# JCarlos_e_Renato.net
KiCad netlist of a schematic drawn in EAGLE
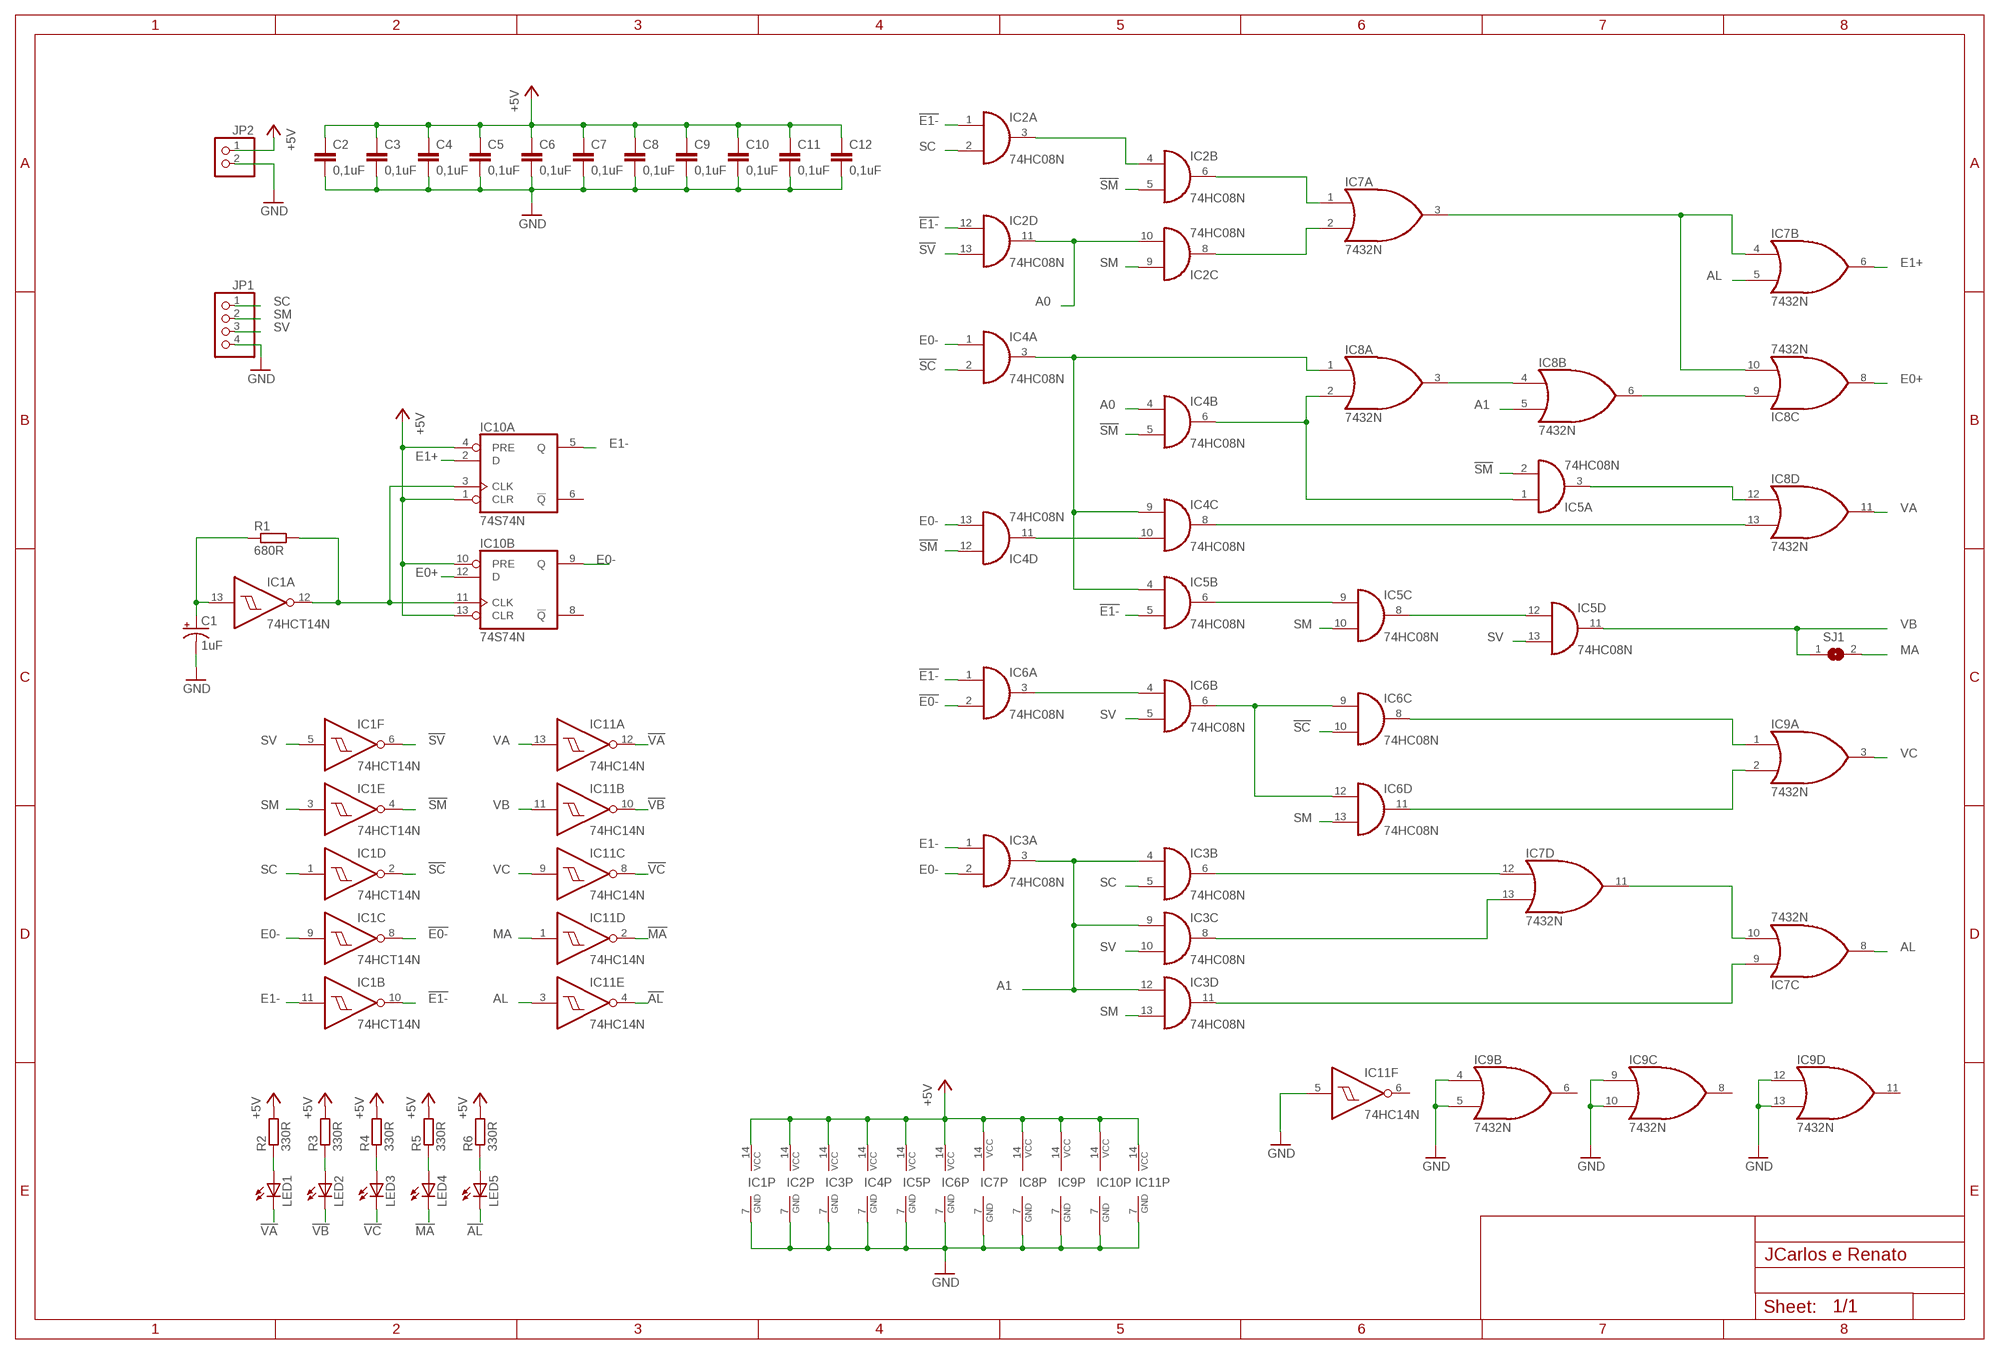
[diagram p0: schematic, sheet 1]

(export (version "E")
  (design (tool "Eeschema 10.0.6"))
  (components
    (comp (ref "C1")
      (value "1uF")
      (footprint "eagle-import:E5-6")
      (libsource (lib "eagle-import") (part "CPOL-USE5-6"))
    )
    (comp (ref "C2")
      (value "0,1uF")
      (footprint "eagle-import:C050-025X075")
      (libsource (lib "eagle-import") (part "C-EU050-025X075"))
    )
    (comp (ref "C3")
      (value "0,1uF")
      (footprint "eagle-import:C050-025X075")
      (libsource (lib "eagle-import") (part "C-EU050-025X075"))
    )
    (comp (ref "C4")
      (value "0,1uF")
      (footprint "eagle-import:C050-025X075")
      (libsource (lib "eagle-import") (part "C-EU050-025X075"))
    )
    (comp (ref "C5")
      (value "0,1uF")
      (footprint "eagle-import:C050-025X075")
      (libsource (lib "eagle-import") (part "C-EU050-025X075"))
    )
    (comp (ref "C6")
      (value "0,1uF")
      (footprint "eagle-import:C050-025X075")
      (libsource (lib "eagle-import") (part "C-EU050-025X075"))
    )
    (comp (ref "C7")
      (value "0,1uF")
      (footprint "eagle-import:C050-025X075")
      (libsource (lib "eagle-import") (part "C-EU050-025X075"))
    )
    (comp (ref "C8")
      (value "0,1uF")
      (footprint "eagle-import:C050-025X075")
      (libsource (lib "eagle-import") (part "C-EU050-025X075"))
    )
    (comp (ref "C9")
      (value "0,1uF")
      (footprint "eagle-import:C050-025X075")
      (libsource (lib "eagle-import") (part "C-EU050-025X075"))
    )
    (comp (ref "C10")
      (value "0,1uF")
      (footprint "eagle-import:C050-025X075")
      (libsource (lib "eagle-import") (part "C-EU050-025X075"))
    )
    (comp (ref "C11")
      (value "0,1uF")
      (footprint "eagle-import:C050-025X075")
      (libsource (lib "eagle-import") (part "C-EU050-025X075"))
    )
    (comp (ref "C12")
      (value "0,1uF")
      (footprint "eagle-import:C050-025X075")
      (libsource (lib "eagle-import") (part "C-EU050-025X075"))
    )
    (comp (ref "IC1")
      (value "74HCT14N")
      (footprint "eagle-import:DIL14")
      (libsource (lib "eagle-import") (part "7414NHCT"))
    )
    (comp (ref "IC2")
      (value "74HC08N")
      (footprint "eagle-import:DIL14")
      (libsource (lib "eagle-import") (part "7408NHC"))
    )
    (comp (ref "IC3")
      (value "74HC08N")
      (footprint "eagle-import:DIL14")
      (libsource (lib "eagle-import") (part "7408NHC"))
    )
    (comp (ref "IC4")
      (value "74HC08N")
      (footprint "eagle-import:DIL14")
      (libsource (lib "eagle-import") (part "7408NHC"))
    )
    (comp (ref "IC5")
      (value "74HC08N")
      (footprint "eagle-import:DIL14")
      (libsource (lib "eagle-import") (part "7408NHC"))
    )
    (comp (ref "IC6")
      (value "74HC08N")
      (footprint "eagle-import:DIL14")
      (libsource (lib "eagle-import") (part "7408NHC"))
    )
    (comp (ref "IC7")
      (value "7432N")
      (footprint "eagle-import:DIL14")
      (libsource (lib "eagle-import") (part "7432N"))
    )
    (comp (ref "IC8")
      (value "7432N")
      (footprint "eagle-import:DIL14")
      (libsource (lib "eagle-import") (part "7432N"))
    )
    (comp (ref "IC9")
      (value "7432N")
      (footprint "eagle-import:DIL14")
      (libsource (lib "eagle-import") (part "7432N"))
    )
    (comp (ref "IC10")
      (value "74S74N")
      (footprint "eagle-import:DIL14")
      (libsource (lib "eagle-import") (part "7474NS"))
    )
    (comp (ref "IC11")
      (value "74HC14N")
      (footprint "eagle-import:DIL14")
      (libsource (lib "eagle-import") (part "7414NHC"))
    )
    (comp (ref "JP1")
      (value "PINHD-1X4")
      (footprint "eagle-import:1X04")
      (libsource (lib "eagle-import") (part "PINHD-1X4"))
    )
    (comp (ref "JP2")
      (value "PINHD-1X2")
      (footprint "eagle-import:1X02")
      (libsource (lib "eagle-import") (part "PINHD-1X2"))
    )
    (comp (ref "LED1")
      (value "LED5MM")
      (footprint "eagle-import:LED5MM")
      (libsource (lib "eagle-import") (part "LED5MM"))
    )
    (comp (ref "LED2")
      (value "LED5MM")
      (footprint "eagle-import:LED5MM")
      (libsource (lib "eagle-import") (part "LED5MM"))
    )
    (comp (ref "LED3")
      (value "LED5MM")
      (footprint "eagle-import:LED5MM")
      (libsource (lib "eagle-import") (part "LED5MM"))
    )
    (comp (ref "LED4")
      (value "LED5MM")
      (footprint "eagle-import:LED5MM")
      (libsource (lib "eagle-import") (part "LED5MM"))
    )
    (comp (ref "LED5")
      (value "LED5MM")
      (footprint "eagle-import:LED5MM")
      (libsource (lib "eagle-import") (part "LED5MM"))
    )
    (comp (ref "R1")
      (value "680R")
      (footprint "eagle-import:0204_5")
      (libsource (lib "eagle-import") (part "R-EU_0204/5"))
    )
    (comp (ref "R2")
      (value "330R")
      (footprint "eagle-import:0207_10")
      (libsource (lib "eagle-import") (part "R-EU_0207/10"))
    )
    (comp (ref "R3")
      (value "330R")
      (footprint "eagle-import:0207_10")
      (libsource (lib "eagle-import") (part "R-EU_0207/10"))
    )
    (comp (ref "R4")
      (value "330R")
      (footprint "eagle-import:0207_10")
      (libsource (lib "eagle-import") (part "R-EU_0207/10"))
    )
    (comp (ref "R5")
      (value "330R")
      (footprint "eagle-import:0207_10")
      (libsource (lib "eagle-import") (part "R-EU_0207/10"))
    )
    (comp (ref "R6")
      (value "330R")
      (footprint "eagle-import:0207_10")
      (libsource (lib "eagle-import") (part "R-EU_0207/10"))
    )
    (comp (ref "SJ1") (value "SJ") (footprint "eagle-import:SJ") (libsource (lib "eagle-import") (part "SJ")))
  )
  (nets
    (net (code "1") (name "+5V") (class "Default")
      (node (ref "C10") (pin "1") (pinfunction "1_1") (pintype "passive"))
      (node (ref "C11") (pin "1") (pinfunction "1_1") (pintype "passive"))
      (node (ref "C12") (pin "1") (pinfunction "1_1") (pintype "passive"))
      (node (ref "C2") (pin "1") (pinfunction "1_1") (pintype "passive"))
      (node (ref "C3") (pin "1") (pinfunction "1_1") (pintype "passive"))
      (node (ref "C4") (pin "1") (pinfunction "1_1") (pintype "passive"))
      (node (ref "C5") (pin "1") (pinfunction "1_1") (pintype "passive"))
      (node (ref "C6") (pin "1") (pinfunction "1_1") (pintype "passive"))
      (node (ref "C7") (pin "1") (pinfunction "1_1") (pintype "passive"))
      (node (ref "C8") (pin "1") (pinfunction "1_1") (pintype "passive"))
      (node (ref "C9") (pin "1") (pinfunction "1_1") (pintype "passive"))
      (node (ref "IC1") (pin "14") (pinfunction "VCC_14") (pintype "power_in"))
      (node (ref "IC10") (pin "1") (pinfunction "CLR_1") (pintype "input"))
      (node (ref "IC10") (pin "10") (pinfunction "PRE_10") (pintype "input"))
      (node (ref "IC10") (pin "13") (pinfunction "CLR_13") (pintype "input"))
      (node (ref "IC10") (pin "14") (pinfunction "VCC_14") (pintype "power_in"))
      (node (ref "IC10") (pin "4") (pinfunction "PRE_4") (pintype "input"))
      (node (ref "IC11") (pin "14") (pinfunction "VCC_14") (pintype "power_in"))
      (node (ref "IC2") (pin "14") (pinfunction "VCC_14") (pintype "power_in"))
      (node (ref "IC3") (pin "14") (pinfunction "VCC_14") (pintype "power_in"))
      (node (ref "IC4") (pin "14") (pinfunction "VCC_14") (pintype "power_in"))
      (node (ref "IC5") (pin "14") (pinfunction "VCC_14") (pintype "power_in"))
      (node (ref "IC6") (pin "14") (pinfunction "VCC_14") (pintype "power_in"))
      (node (ref "IC7") (pin "14") (pinfunction "VCC_14") (pintype "power_in"))
      (node (ref "IC8") (pin "14") (pinfunction "VCC_14") (pintype "power_in"))
      (node (ref "IC9") (pin "14") (pinfunction "VCC_14") (pintype "power_in"))
      (node (ref "JP2") (pin "1") (pinfunction "1_1") (pintype "passive"))
      (node (ref "R2") (pin "2") (pinfunction "2_2") (pintype "passive"))
      (node (ref "R3") (pin "2") (pinfunction "2_2") (pintype "passive"))
      (node (ref "R4") (pin "2") (pinfunction "2_2") (pintype "passive"))
      (node (ref "R5") (pin "2") (pinfunction "2_2") (pintype "passive"))
      (node (ref "R6") (pin "2") (pinfunction "2_2") (pintype "passive"))
    )
    (net (code "2") (name "/A0") (class "Default")
      (node (ref "IC2") (pin "10") (pinfunction "I1_10") (pintype "input"))
      (node (ref "IC2") (pin "11") (pinfunction "O_11") (pintype "output"))
      (node (ref "IC4") (pin "4") (pinfunction "I0_4") (pintype "input"))
    )
    (net (code "3") (name "/A1") (class "Default")
      (node (ref "IC3") (pin "12") (pinfunction "I0_12") (pintype "input"))
      (node (ref "IC3") (pin "3") (pinfunction "O_3") (pintype "output"))
      (node (ref "IC3") (pin "4") (pinfunction "I0_4") (pintype "input"))
      (node (ref "IC3") (pin "9") (pinfunction "I0_9") (pintype "input"))
      (node (ref "IC8") (pin "5") (pinfunction "I1_5") (pintype "input"))
    )
    (net (code "4") (name "/AL") (class "Default")
      (node (ref "IC11") (pin "3") (pinfunction "I_3") (pintype "input"))
      (node (ref "IC7") (pin "5") (pinfunction "I1_5") (pintype "input"))
      (node (ref "IC7") (pin "8") (pinfunction "O_8") (pintype "output"))
    )
    (net (code "5") (name "/E0+") (class "Default")
      (node (ref "IC10") (pin "12") (pinfunction "D_12") (pintype "input"))
      (node (ref "IC8") (pin "8") (pinfunction "O_8") (pintype "output"))
    )
    (net (code "6") (name "/E0-") (class "Default")
      (node (ref "IC1") (pin "9") (pinfunction "I_9") (pintype "input"))
      (node (ref "IC10") (pin "9") (pinfunction "Q_9") (pintype "output"))
      (node (ref "IC3") (pin "2") (pinfunction "I1_2") (pintype "input"))
      (node (ref "IC4") (pin "1") (pinfunction "I0_1") (pintype "input"))
      (node (ref "IC4") (pin "13") (pinfunction "I1_13") (pintype "input"))
    )
    (net (code "7") (name "/E1+") (class "Default")
      (node (ref "IC10") (pin "2") (pinfunction "D_2") (pintype "input"))
      (node (ref "IC7") (pin "6") (pinfunction "O_6") (pintype "output"))
    )
    (net (code "8") (name "/E1-") (class "Default")
      (node (ref "IC1") (pin "11") (pinfunction "I_11") (pintype "input"))
      (node (ref "IC10") (pin "5") (pinfunction "Q_5") (pintype "output"))
      (node (ref "IC3") (pin "1") (pinfunction "I0_1") (pintype "input"))
    )
    (net (code "9") (name "/MA") (class "Default")
      (node (ref "IC11") (pin "1") (pinfunction "I_1") (pintype "input"))
      (node (ref "SJ1") (pin "2") (pinfunction "2_2") (pintype "passive"))
    )
    (net (code "10") (name "/SC") (class "Default")
      (node (ref "IC1") (pin "1") (pinfunction "I_1") (pintype "input"))
      (node (ref "IC2") (pin "2") (pinfunction "I1_2") (pintype "input"))
      (node (ref "IC3") (pin "5") (pinfunction "I1_5") (pintype "input"))
      (node (ref "JP1") (pin "1") (pinfunction "1_1") (pintype "passive"))
    )
    (net (code "11") (name "/SM") (class "Default")
      (node (ref "IC1") (pin "3") (pinfunction "I_3") (pintype "input"))
      (node (ref "IC2") (pin "9") (pinfunction "I0_9") (pintype "input"))
      (node (ref "IC3") (pin "13") (pinfunction "I1_13") (pintype "input"))
      (node (ref "IC5") (pin "10") (pinfunction "I1_10") (pintype "input"))
      (node (ref "IC6") (pin "13") (pinfunction "I1_13") (pintype "input"))
      (node (ref "JP1") (pin "2") (pinfunction "2_2") (pintype "passive"))
    )
    (net (code "12") (name "/SV") (class "Default")
      (node (ref "IC1") (pin "5") (pinfunction "I_5") (pintype "input"))
      (node (ref "IC3") (pin "10") (pinfunction "I1_10") (pintype "input"))
      (node (ref "IC5") (pin "13") (pinfunction "I1_13") (pintype "input"))
      (node (ref "IC6") (pin "5") (pinfunction "I1_5") (pintype "input"))
      (node (ref "JP1") (pin "3") (pinfunction "3_3") (pintype "passive"))
    )
    (net (code "13") (name "/VA") (class "Default")
      (node (ref "IC11") (pin "13") (pinfunction "I_13") (pintype "input"))
      (node (ref "IC8") (pin "11") (pinfunction "O_11") (pintype "output"))
    )
    (net (code "14") (name "/VB") (class "Default")
      (node (ref "IC11") (pin "11") (pinfunction "I_11") (pintype "input"))
      (node (ref "IC5") (pin "11") (pinfunction "O_11") (pintype "output"))
      (node (ref "SJ1") (pin "1") (pinfunction "1_1") (pintype "passive"))
    )
    (net (code "15") (name "/VC") (class "Default")
      (node (ref "IC11") (pin "9") (pinfunction "I_9") (pintype "input"))
      (node (ref "IC9") (pin "3") (pinfunction "O_3") (pintype "output"))
    )
    (net (code "16") (name "/~{AL}") (class "Default")
      (node (ref "IC11") (pin "4") (pinfunction "O_4") (pintype "output"))
      (node (ref "LED5") (pin "K") (pinfunction "C_K") (pintype "passive"))
    )
    (net (code "17") (name "/~{E0-}") (class "Default")
      (node (ref "IC1") (pin "8") (pinfunction "O_8") (pintype "output"))
      (node (ref "IC6") (pin "2") (pinfunction "I1_2") (pintype "input"))
    )
    (net (code "18") (name "/~{E1-}") (class "Default")
      (node (ref "IC1") (pin "10") (pinfunction "O_10") (pintype "output"))
      (node (ref "IC2") (pin "1") (pinfunction "I0_1") (pintype "input"))
      (node (ref "IC2") (pin "12") (pinfunction "I0_12") (pintype "input"))
      (node (ref "IC5") (pin "5") (pinfunction "I1_5") (pintype "input"))
      (node (ref "IC6") (pin "1") (pinfunction "I0_1") (pintype "input"))
    )
    (net (code "19") (name "/~{MA}") (class "Default")
      (node (ref "IC11") (pin "2") (pinfunction "O_2") (pintype "output"))
      (node (ref "LED4") (pin "K") (pinfunction "C_K") (pintype "passive"))
    )
    (net (code "20") (name "/~{SC}") (class "Default")
      (node (ref "IC1") (pin "2") (pinfunction "O_2") (pintype "output"))
      (node (ref "IC4") (pin "2") (pinfunction "I1_2") (pintype "input"))
      (node (ref "IC6") (pin "10") (pinfunction "I1_10") (pintype "input"))
    )
    (net (code "21") (name "/~{SM}") (class "Default")
      (node (ref "IC1") (pin "4") (pinfunction "O_4") (pintype "output"))
      (node (ref "IC2") (pin "5") (pinfunction "I1_5") (pintype "input"))
      (node (ref "IC4") (pin "12") (pinfunction "I0_12") (pintype "input"))
      (node (ref "IC4") (pin "5") (pinfunction "I1_5") (pintype "input"))
      (node (ref "IC5") (pin "2") (pinfunction "I1_2") (pintype "input"))
    )
    (net (code "22") (name "/~{SV}") (class "Default")
      (node (ref "IC1") (pin "6") (pinfunction "O_6") (pintype "output"))
      (node (ref "IC2") (pin "13") (pinfunction "I1_13") (pintype "input"))
    )
    (net (code "23") (name "/~{VA}") (class "Default")
      (node (ref "IC11") (pin "12") (pinfunction "O_12") (pintype "output"))
      (node (ref "LED1") (pin "K") (pinfunction "C_K") (pintype "passive"))
    )
    (net (code "24") (name "/~{VB}") (class "Default")
      (node (ref "IC11") (pin "10") (pinfunction "O_10") (pintype "output"))
      (node (ref "LED2") (pin "K") (pinfunction "C_K") (pintype "passive"))
    )
    (net (code "25") (name "/~{VC}") (class "Default")
      (node (ref "IC11") (pin "8") (pinfunction "O_8") (pintype "output"))
      (node (ref "LED3") (pin "K") (pinfunction "C_K") (pintype "passive"))
    )
    (net (code "26") (name "GND") (class "Default")
      (node (ref "C1") (pin "-") (pinfunction "-_-") (pintype "passive"))
      (node (ref "C10") (pin "2") (pinfunction "2_2") (pintype "passive"))
      (node (ref "C11") (pin "2") (pinfunction "2_2") (pintype "passive"))
      (node (ref "C12") (pin "2") (pinfunction "2_2") (pintype "passive"))
      (node (ref "C2") (pin "2") (pinfunction "2_2") (pintype "passive"))
      (node (ref "C3") (pin "2") (pinfunction "2_2") (pintype "passive"))
      (node (ref "C4") (pin "2") (pinfunction "2_2") (pintype "passive"))
      (node (ref "C5") (pin "2") (pinfunction "2_2") (pintype "passive"))
      (node (ref "C6") (pin "2") (pinfunction "2_2") (pintype "passive"))
      (node (ref "C7") (pin "2") (pinfunction "2_2") (pintype "passive"))
      (node (ref "C8") (pin "2") (pinfunction "2_2") (pintype "passive"))
      (node (ref "C9") (pin "2") (pinfunction "2_2") (pintype "passive"))
      (node (ref "IC1") (pin "7") (pinfunction "GND_7") (pintype "power_in"))
      (node (ref "IC10") (pin "7") (pinfunction "GND_7") (pintype "power_in"))
      (node (ref "IC11") (pin "5") (pinfunction "I_5") (pintype "input"))
      (node (ref "IC11") (pin "7") (pinfunction "GND_7") (pintype "power_in"))
      (node (ref "IC2") (pin "7") (pinfunction "GND_7") (pintype "power_in"))
      (node (ref "IC3") (pin "7") (pinfunction "GND_7") (pintype "power_in"))
      (node (ref "IC4") (pin "7") (pinfunction "GND_7") (pintype "power_in"))
      (node (ref "IC5") (pin "7") (pinfunction "GND_7") (pintype "power_in"))
      (node (ref "IC6") (pin "7") (pinfunction "GND_7") (pintype "power_in"))
      (node (ref "IC7") (pin "7") (pinfunction "GND_7") (pintype "power_in"))
      (node (ref "IC8") (pin "7") (pinfunction "GND_7") (pintype "power_in"))
      (node (ref "IC9") (pin "10") (pinfunction "I1_10") (pintype "input"))
      (node (ref "IC9") (pin "12") (pinfunction "I0_12") (pintype "input"))
      (node (ref "IC9") (pin "13") (pinfunction "I1_13") (pintype "input"))
      (node (ref "IC9") (pin "4") (pinfunction "I0_4") (pintype "input"))
      (node (ref "IC9") (pin "5") (pinfunction "I1_5") (pintype "input"))
      (node (ref "IC9") (pin "7") (pinfunction "GND_7") (pintype "power_in"))
      (node (ref "IC9") (pin "9") (pinfunction "I0_9") (pintype "input"))
      (node (ref "JP1") (pin "4") (pinfunction "4_4") (pintype "passive"))
      (node (ref "JP2") (pin "2") (pinfunction "2_2") (pintype "passive"))
    )
    (net (code "27") (name "Net-(IC1A-I)") (class "Default")
      (node (ref "C1") (pin "+") (pinfunction "+_+") (pintype "passive"))
      (node (ref "IC1") (pin "13") (pinfunction "I_13") (pintype "input"))
      (node (ref "R1") (pin "1") (pinfunction "1_1") (pintype "passive"))
    )
    (net (code "28") (name "Net-(IC2A-O)") (class "Default")
      (node (ref "IC2") (pin "3") (pinfunction "O_3") (pintype "output"))
      (node (ref "IC2") (pin "4") (pinfunction "I0_4") (pintype "input"))
    )
    (net (code "29") (name "Net-(IC2B-O)") (class "Default")
      (node (ref "IC2") (pin "6") (pinfunction "O_6") (pintype "output"))
      (node (ref "IC7") (pin "1") (pinfunction "I0_1") (pintype "input"))
    )
    (net (code "30") (name "Net-(IC2C-O)") (class "Default")
      (node (ref "IC2") (pin "8") (pinfunction "O_8") (pintype "output"))
      (node (ref "IC7") (pin "2") (pinfunction "I1_2") (pintype "input"))
    )
    (net (code "31") (name "Net-(IC3B-O)") (class "Default")
      (node (ref "IC3") (pin "6") (pinfunction "O_6") (pintype "output"))
      (node (ref "IC7") (pin "12") (pinfunction "I0_12") (pintype "input"))
    )
    (net (code "32") (name "Net-(IC3C-O)") (class "Default")
      (node (ref "IC3") (pin "8") (pinfunction "O_8") (pintype "output"))
      (node (ref "IC7") (pin "13") (pinfunction "I1_13") (pintype "input"))
    )
    (net (code "33") (name "Net-(IC3D-O)") (class "Default")
      (node (ref "IC3") (pin "11") (pinfunction "O_11") (pintype "output"))
      (node (ref "IC7") (pin "9") (pinfunction "I0_9") (pintype "input"))
    )
    (net (code "34") (name "Net-(IC4A-O)") (class "Default")
      (node (ref "IC4") (pin "3") (pinfunction "O_3") (pintype "output"))
      (node (ref "IC4") (pin "9") (pinfunction "I0_9") (pintype "input"))
      (node (ref "IC5") (pin "4") (pinfunction "I0_4") (pintype "input"))
      (node (ref "IC8") (pin "1") (pinfunction "I0_1") (pintype "input"))
    )
    (net (code "35") (name "Net-(IC4B-O)") (class "Default")
      (node (ref "IC4") (pin "6") (pinfunction "O_6") (pintype "output"))
      (node (ref "IC5") (pin "1") (pinfunction "I0_1") (pintype "input"))
      (node (ref "IC8") (pin "2") (pinfunction "I1_2") (pintype "input"))
    )
    (net (code "36") (name "Net-(IC4C-I1)") (class "Default")
      (node (ref "IC4") (pin "10") (pinfunction "I1_10") (pintype "input"))
      (node (ref "IC4") (pin "11") (pinfunction "O_11") (pintype "output"))
    )
    (net (code "37") (name "Net-(IC4C-O)") (class "Default")
      (node (ref "IC4") (pin "8") (pinfunction "O_8") (pintype "output"))
      (node (ref "IC8") (pin "13") (pinfunction "I1_13") (pintype "input"))
    )
    (net (code "38") (name "Net-(IC5A-O)") (class "Default")
      (node (ref "IC5") (pin "3") (pinfunction "O_3") (pintype "output"))
      (node (ref "IC8") (pin "12") (pinfunction "I0_12") (pintype "input"))
    )
    (net (code "39") (name "Net-(IC5B-O)") (class "Default")
      (node (ref "IC5") (pin "6") (pinfunction "O_6") (pintype "output"))
      (node (ref "IC5") (pin "9") (pinfunction "I0_9") (pintype "input"))
    )
    (net (code "40") (name "Net-(IC5C-O)") (class "Default")
      (node (ref "IC5") (pin "12") (pinfunction "I0_12") (pintype "input"))
      (node (ref "IC5") (pin "8") (pinfunction "O_8") (pintype "output"))
    )
    (net (code "41") (name "Net-(IC6A-O)") (class "Default")
      (node (ref "IC6") (pin "3") (pinfunction "O_3") (pintype "output"))
      (node (ref "IC6") (pin "4") (pinfunction "I0_4") (pintype "input"))
    )
    (net (code "42") (name "Net-(IC6B-O)") (class "Default")
      (node (ref "IC6") (pin "12") (pinfunction "I0_12") (pintype "input"))
      (node (ref "IC6") (pin "6") (pinfunction "O_6") (pintype "output"))
      (node (ref "IC6") (pin "9") (pinfunction "I0_9") (pintype "input"))
    )
    (net (code "43") (name "Net-(IC6C-O)") (class "Default")
      (node (ref "IC6") (pin "8") (pinfunction "O_8") (pintype "output"))
      (node (ref "IC9") (pin "1") (pinfunction "I0_1") (pintype "input"))
    )
    (net (code "44") (name "Net-(IC6D-O)") (class "Default")
      (node (ref "IC6") (pin "11") (pinfunction "O_11") (pintype "output"))
      (node (ref "IC9") (pin "2") (pinfunction "I1_2") (pintype "input"))
    )
    (net (code "45") (name "Net-(IC7A-O)") (class "Default")
      (node (ref "IC7") (pin "3") (pinfunction "O_3") (pintype "output"))
      (node (ref "IC7") (pin "4") (pinfunction "I0_4") (pintype "input"))
      (node (ref "IC8") (pin "10") (pinfunction "I1_10") (pintype "input"))
    )
    (net (code "46") (name "Net-(IC7C-I1)") (class "Default")
      (node (ref "IC7") (pin "10") (pinfunction "I1_10") (pintype "input"))
      (node (ref "IC7") (pin "11") (pinfunction "O_11") (pintype "output"))
    )
    (net (code "47") (name "Net-(IC8A-O)") (class "Default")
      (node (ref "IC8") (pin "3") (pinfunction "O_3") (pintype "output"))
      (node (ref "IC8") (pin "4") (pinfunction "I0_4") (pintype "input"))
    )
    (net (code "48") (name "Net-(IC8B-O)") (class "Default")
      (node (ref "IC8") (pin "6") (pinfunction "O_6") (pintype "output"))
      (node (ref "IC8") (pin "9") (pinfunction "I0_9") (pintype "input"))
    )
    (net (code "49") (name "Net-(IC10A-CLK)") (class "Default")
      (node (ref "IC1") (pin "12") (pinfunction "O_12") (pintype "output"))
      (node (ref "IC10") (pin "11") (pinfunction "CLK_11") (pintype "input"))
      (node (ref "IC10") (pin "3") (pinfunction "CLK_3") (pintype "input"))
      (node (ref "R1") (pin "2") (pinfunction "2_2") (pintype "passive"))
    )
    (net (code "50") (name "Net-(LED1-PadA)") (class "Default")
      (node (ref "LED1") (pin "A") (pinfunction "A_A") (pintype "passive"))
      (node (ref "R2") (pin "1") (pinfunction "1_1") (pintype "passive"))
    )
    (net (code "51") (name "Net-(LED2-PadA)") (class "Default")
      (node (ref "LED2") (pin "A") (pinfunction "A_A") (pintype "passive"))
      (node (ref "R3") (pin "1") (pinfunction "1_1") (pintype "passive"))
    )
    (net (code "52") (name "Net-(LED3-PadA)") (class "Default")
      (node (ref "LED3") (pin "A") (pinfunction "A_A") (pintype "passive"))
      (node (ref "R4") (pin "1") (pinfunction "1_1") (pintype "passive"))
    )
    (net (code "53") (name "Net-(LED4-PadA)") (class "Default")
      (node (ref "LED4") (pin "A") (pinfunction "A_A") (pintype "passive"))
      (node (ref "R5") (pin "1") (pinfunction "1_1") (pintype "passive"))
    )
    (net (code "54") (name "Net-(LED5-PadA)") (class "Default")
      (node (ref "LED5") (pin "A") (pinfunction "A_A") (pintype "passive"))
      (node (ref "R6") (pin "1") (pinfunction "1_1") (pintype "passive"))
    )
    (net (code "55") (name "unconnected-(IC9B-O-Pad6)") (class "Default")
      (node (ref "IC9") (pin "6") (pinfunction "O_6") (pintype "output"))
    )
    (net (code "56") (name "unconnected-(IC9C-O-Pad8)") (class "Default")
      (node (ref "IC9") (pin "8") (pinfunction "O_8") (pintype "output"))
    )
    (net (code "57") (name "unconnected-(IC9D-O-Pad11)") (class "Default")
      (node (ref "IC9") (pin "11") (pinfunction "O_11") (pintype "output"))
    )
    (net (code "58") (name "unconnected-(IC10A-~{Q}-Pad6)") (class "Default")
      (node (ref "IC10") (pin "6") (pinfunction "~{Q}_6") (pintype "output"))
    )
    (net (code "59") (name "unconnected-(IC10B-~{Q}-Pad8)") (class "Default")
      (node (ref "IC10") (pin "8") (pinfunction "~{Q}_8") (pintype "output"))
    )
    (net (code "60") (name "unconnected-(IC11F-O-Pad6)") (class "Default")
      (node (ref "IC11") (pin "6") (pinfunction "O_6") (pintype "output"))
    )
  )
)
